# DRV10987.net
KiCad netlist of a schematic drawn in EAGLE
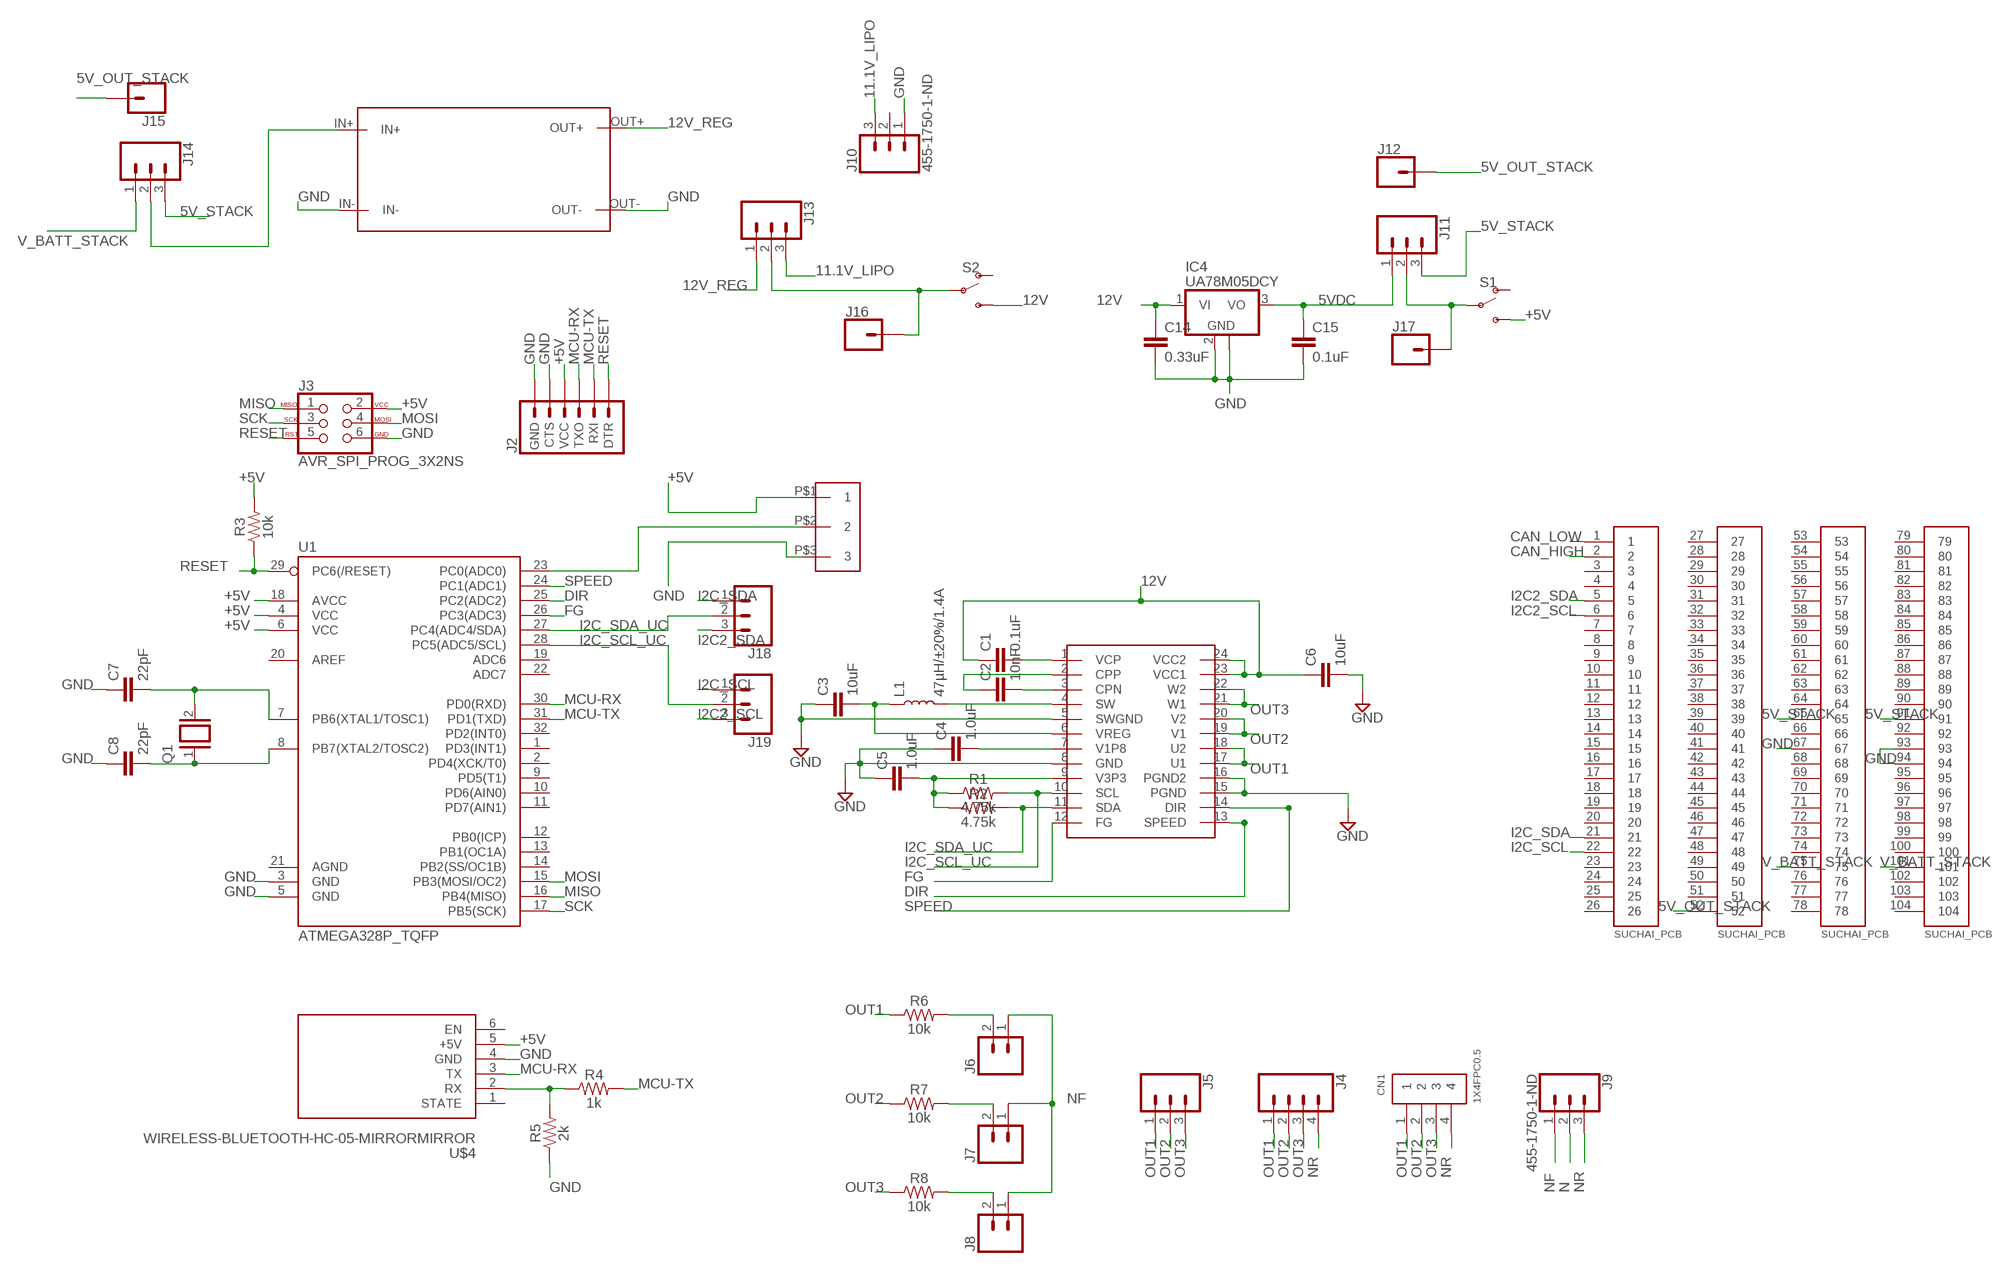
[diagram p0: schematic, sheet 1]

(export (version "E")
  (design (tool "Eeschema 10.0.6"))
  (components
    (comp (ref "C1")
      (value "0.1uF")
      (footprint "eagle-import:0805")
      (libsource (lib "eagle-import") (part "1.0UF-0805-25V-10%"))
    )
    (comp (ref "C2")
      (value "10nF")
      (footprint "eagle-import:0805")
      (libsource (lib "eagle-import") (part "1.0UF-0805-25V-10%"))
    )
    (comp (ref "C3")
      (value "10uF")
      (footprint "eagle-import:0805")
      (libsource (lib "eagle-import") (part "1.0UF-0805-25V-10%"))
    )
    (comp (ref "C4")
      (value "1.0uF")
      (footprint "eagle-import:0805")
      (libsource (lib "eagle-import") (part "1.0UF-0805-25V-10%"))
    )
    (comp (ref "C5")
      (value "1.0uF")
      (footprint "eagle-import:0805")
      (libsource (lib "eagle-import") (part "1.0UF-0805-25V-10%"))
    )
    (comp (ref "C6")
      (value "10uF")
      (footprint "eagle-import:0805")
      (libsource (lib "eagle-import") (part "1.0UF-0805-25V-10%"))
    )
    (comp (ref "C7")
      (value "22pF")
      (footprint "eagle-import:1206")
      (libsource (lib "eagle-import") (part "2.2UF-1206-50V-10%"))
    )
    (comp (ref "C8")
      (value "22pF")
      (footprint "eagle-import:1206")
      (libsource (lib "eagle-import") (part "2.2UF-1206-50V-10%"))
    )
    (comp (ref "C14")
      (value "0.33uF")
      (footprint "eagle-import:1206")
      (libsource (lib "eagle-import") (part "1.0UF-1206-50V-10%"))
    )
    (comp (ref "C15")
      (value "0.1uF")
      (footprint "eagle-import:1206")
      (libsource (lib "eagle-import") (part "1.0UF-1206-50V-10%"))
    )
    (comp (ref "CN1")
      (value "1X4FPC0.5")
      (footprint "eagle-import:FPC_0.5MM-4")
      (libsource (lib "eagle-import") (part "1X4FPC0.5"))
    )
    (comp (ref "IC4")
      (value "UA78M05DCY")
      (footprint "eagle-import:SOT223")
      (libsource (lib "eagle-import") (part "UA78MDCY05"))
    )
    (comp (ref "J1")
      (value "SUCHAI_PCB")
      (footprint "eagle-import:SUCHAI_PCB")
      (libsource (lib "eagle-import") (part "SUCHAI_PCB"))
    )
    (comp (ref "J2")
      (value "6_PIN_SERIAL_TARGET")
      (footprint "eagle-import:1X06")
      (libsource (lib "eagle-import") (part "6_PIN_SERIAL_TARGET"))
    )
    (comp (ref "J3")
      (value "AVR_SPI_PROG_3X2NS")
      (footprint "eagle-import:2X3-NS")
      (libsource (lib "eagle-import") (part "AVR_SPI_PROG_3X2NS"))
    )
    (comp (ref "J4")
      (value "CONN_04")
      (footprint "eagle-import:1X04")
      (libsource (lib "eagle-import") (part "CONN_04"))
    )
    (comp (ref "J5")
      (value "CONN_03-SCREW-5MM")
      (footprint "eagle-import:SCREWTERMINAL-5MM-3")
      (libsource (lib "eagle-import") (part "CONN_03-SCREW-5MM"))
    )
    (comp (ref "J6")
      (value "CONN_02")
      (footprint "eagle-import:1X02")
      (libsource (lib "eagle-import") (part "CONN_02"))
    )
    (comp (ref "J7")
      (value "CONN_02")
      (footprint "eagle-import:1X02")
      (libsource (lib "eagle-import") (part "CONN_02"))
    )
    (comp (ref "J8")
      (value "CONN_02")
      (footprint "eagle-import:1X02")
      (libsource (lib "eagle-import") (part "CONN_02"))
    )
    (comp (ref "J9")
      (value "455-1750-1-ND")
      (footprint "eagle-import:1X03")
      (libsource (lib "eagle-import") (part "CONN_03"))
    )
    (comp (ref "J10")
      (value "455-1750-1-ND")
      (footprint "eagle-import:1X03")
      (libsource (lib "eagle-import") (part "CONN_03"))
    )
    (comp (ref "J11")
      (value "CONN_03LOCK")
      (footprint "eagle-import:1X03_LOCK")
      (libsource (lib "eagle-import") (part "CONN_03LOCK"))
    )
    (comp (ref "J12")
      (value "CONN_01")
      (footprint "eagle-import:1X01")
      (libsource (lib "eagle-import") (part "CONN_01"))
    )
    (comp (ref "J13")
      (value "CONN_03LOCK")
      (footprint "eagle-import:1X03_LOCK")
      (libsource (lib "eagle-import") (part "CONN_03LOCK"))
    )
    (comp (ref "J14")
      (value "CONN_03LOCK")
      (footprint "eagle-import:1X03_LOCK")
      (libsource (lib "eagle-import") (part "CONN_03LOCK"))
    )
    (comp (ref "J15")
      (value "CONN_01")
      (footprint "eagle-import:1X01")
      (libsource (lib "eagle-import") (part "CONN_01"))
    )
    (comp (ref "J16")
      (value "CONN_01")
      (footprint "eagle-import:1X01")
      (libsource (lib "eagle-import") (part "CONN_01"))
    )
    (comp (ref "J17")
      (value "CONN_01")
      (footprint "eagle-import:1X01")
      (libsource (lib "eagle-import") (part "CONN_01"))
    )
    (comp (ref "J18")
      (value "CONN_03LOCK")
      (footprint "eagle-import:1X03_LOCK")
      (libsource (lib "eagle-import") (part "CONN_03LOCK"))
    )
    (comp (ref "J19")
      (value "CONN_03LOCK")
      (footprint "eagle-import:1X03_LOCK")
      (libsource (lib "eagle-import") (part "CONN_03LOCK"))
    )
    (comp (ref "L1")
      (value "47µH/±20%/1.4A")
      (footprint "eagle-import:SRN6045")
      (libsource (lib "eagle-import") (part "INDUCTOR-SRN6045-33UH"))
    )
    (comp (ref "Q1")
      (value "XTAL/S")
      (footprint "eagle-import:QS")
      (libsource (lib "eagle-import") (part "XTAL/S"))
    )
    (comp (ref "R1")
      (value "4.75k")
      (footprint "eagle-import:0805")
      (libsource (lib "eagle-import") (part "RESISTOR0805"))
    )
    (comp (ref "R2")
      (value "4.75k")
      (footprint "eagle-import:0805")
      (libsource (lib "eagle-import") (part "RESISTOR0805"))
    )
    (comp (ref "R3")
      (value "10k")
      (footprint "eagle-import:1206")
      (libsource (lib "eagle-import") (part "RESISTOR1206"))
    )
    (comp (ref "R4")
      (value "1k")
      (footprint "eagle-import:AXIAL-0.3")
      (libsource (lib "eagle-import") (part "1KOHM-HORIZ-1/4W-5%"))
    )
    (comp (ref "R5")
      (value "2k")
      (footprint "eagle-import:AXIAL-0.3")
      (libsource (lib "eagle-import") (part "resistors-longpads_RESISTORAXIAL-0.3"))
    )
    (comp (ref "R6")
      (value "10k")
      (footprint "eagle-import:AXIAL-0.3")
      (libsource (lib "eagle-import") (part "10KOHM-HORIZ-1/4W-1%"))
    )
    (comp (ref "R7")
      (value "10k")
      (footprint "eagle-import:AXIAL-0.3")
      (libsource (lib "eagle-import") (part "10KOHM-HORIZ-1/4W-1%"))
    )
    (comp (ref "R8")
      (value "10k")
      (footprint "eagle-import:AXIAL-0.3")
      (libsource (lib "eagle-import") (part "10KOHM-HORIZ-1/4W-1%"))
    )
    (comp (ref "S1")
      (value "SWITCH-SPDT-PTH-11.6X4.0MM")
      (footprint "eagle-import:SWITCH_SPDT_PTH_11.6X4.0MM")
      (libsource (lib "eagle-import") (part "SWITCH-SPDT-PTH-11.6X4.0MM"))
    )
    (comp (ref "S2")
      (value "SWITCH-SPDT-PTH-11.6X4.0MM")
      (footprint "eagle-import:SWITCH_SPDT_PTH_11.6X4.0MM")
      (libsource (lib "eagle-import") (part "SWITCH-SPDT-PTH-11.6X4.0MM"))
    )
    (comp (ref "U$1")
      (value "DRV10987")
      (footprint "eagle-import:DRV10987")
      (libsource (lib "eagle-import") (part "DRV10987"))
    )
    (comp (ref "U$2")
      (value "XL6009E1_MODULE")
      (footprint "eagle-import:XL6009E1_MODULE")
      (libsource (lib "eagle-import") (part "XL6009E1_MODULE"))
    )
    (comp (ref "U$3")
      (value "CONN_03_SMD_SMALL")
      (footprint "eagle-import:CONN_03_SMD_SMALL")
      (libsource (lib "eagle-import") (part "CONN_03_SMD_SMALL"))
    )
    (comp (ref "U$4")
      (value "WIRELESS-BLUETOOTH-HC-05-MIRRORMIRROR")
      (footprint "eagle-import:WIRELESS-BLUETOOTH-HC-05-MIRROR")
      (libsource (lib "eagle-import") (part "WIRELESS-BLUETOOTH-HC-05-MIRRORMIRROR"))
    )
    (comp (ref "U1")
      (value "ATMEGA328P_TQFP")
      (footprint "eagle-import:TQFP32-08")
      (libsource (lib "eagle-import") (part "ATMEGA328P_TQFP"))
    )
  )
  (nets
    (net (code "1") (name "/+5V") (class "Default")
      (node (ref "J2") (pin "4") (pinfunction "VCC_4") (pintype "passive"))
      (node (ref "J3") (pin "2") (pinfunction "2_2") (pintype "passive"))
      (node (ref "R3") (pin "2") (pinfunction "2_2") (pintype "passive"))
      (node (ref "S1") (pin "3") (pinfunction "S_3") (pintype "passive"))
      (node (ref "U$3") (pin "P$1") (pinfunction "1_P$1") (pintype "bidirectional"))
      (node (ref "U$4") (pin "5") (pinfunction "+5V_5") (pintype "power_in"))
      (node (ref "U1") (pin "18") (pinfunction "AVCC_18") (pintype "bidirectional"))
      (node (ref "U1") (pin "4") (pinfunction "VCC_4") (pintype "bidirectional"))
      (node (ref "U1") (pin "6") (pinfunction "VCC_6") (pintype "bidirectional"))
    )
    (net (code "2") (name "/5VDC") (class "Default")
      (node (ref "C15") (pin "1") (pinfunction "1_1") (pintype "passive"))
      (node (ref "IC4") (pin "3") (pinfunction "VO_3") (pintype "passive"))
      (node (ref "J11") (pin "1") (pinfunction "1_1") (pintype "passive"))
    )
    (net (code "3") (name "/5V_OUT_STACK") (class "Default")
      (node (ref "J1") (pin "52") (pinfunction "52_52") (pintype "bidirectional"))
      (node (ref "J12") (pin "1") (pinfunction "1_1") (pintype "passive"))
      (node (ref "J15") (pin "1") (pinfunction "1_1") (pintype "passive"))
    )
    (net (code "4") (name "/5V_STACK") (class "Default")
      (node (ref "J1") (pin "65") (pinfunction "65_65") (pintype "bidirectional"))
      (node (ref "J1") (pin "91") (pinfunction "91_91") (pintype "bidirectional"))
      (node (ref "J11") (pin "3") (pinfunction "3_3") (pintype "passive"))
      (node (ref "J14") (pin "3") (pinfunction "3_3") (pintype "passive"))
    )
    (net (code "5") (name "/11.1V_LIPO") (class "Default")
      (node (ref "J10") (pin "3") (pinfunction "3_3") (pintype "passive"))
      (node (ref "J13") (pin "3") (pinfunction "3_3") (pintype "passive"))
    )
    (net (code "6") (name "/12V") (class "Default")
      (node (ref "C1") (pin "1") (pinfunction "1_1") (pintype "passive"))
      (node (ref "C14") (pin "1") (pinfunction "1_1") (pintype "passive"))
      (node (ref "C6") (pin "1") (pinfunction "1_1") (pintype "passive"))
      (node (ref "IC4") (pin "1") (pinfunction "VI_1") (pintype "input"))
      (node (ref "S2") (pin "3") (pinfunction "S_3") (pintype "passive"))
      (node (ref "U$1") (pin "23") (pinfunction "VCC1_23") (pintype "bidirectional"))
      (node (ref "U$1") (pin "24") (pinfunction "VCC2_24") (pintype "bidirectional"))
    )
    (net (code "7") (name "/12V_REG") (class "Default")
      (node (ref "J13") (pin "1") (pinfunction "1_1") (pintype "passive"))
      (node (ref "U$2") (pin "OUT+") (pinfunction "OUT+_OUT+") (pintype "bidirectional"))
    )
    (net (code "8") (name "/CAN_HIGH") (class "Default")
      (node (ref "J1") (pin "2") (pinfunction "2_2") (pintype "bidirectional"))
    )
    (net (code "9") (name "/CAN_LOW") (class "Default")
      (node (ref "J1") (pin "1") (pinfunction "1_1") (pintype "bidirectional"))
    )
    (net (code "10") (name "/DIR") (class "Default")
      (node (ref "U$1") (pin "13") (pinfunction "SPEED_13") (pintype "bidirectional"))
      (node (ref "U1") (pin "25") (pinfunction "PC2(ADC2)_25") (pintype "bidirectional"))
    )
    (net (code "11") (name "/FG") (class "Default")
      (node (ref "U$1") (pin "12") (pinfunction "FG_12") (pintype "bidirectional"))
      (node (ref "U1") (pin "26") (pinfunction "PC3(ADC3)_26") (pintype "bidirectional"))
    )
    (net (code "12") (name "/I2C2_SCL") (class "Default")
      (node (ref "J1") (pin "6") (pinfunction "6_6") (pintype "bidirectional"))
      (node (ref "J19") (pin "3") (pinfunction "3_3") (pintype "passive"))
    )
    (net (code "13") (name "/I2C2_SDA") (class "Default")
      (node (ref "J1") (pin "5") (pinfunction "5_5") (pintype "bidirectional"))
      (node (ref "J18") (pin "3") (pinfunction "3_3") (pintype "passive"))
    )
    (net (code "14") (name "/I2C_SCL") (class "Default")
      (node (ref "J1") (pin "22") (pinfunction "22_22") (pintype "bidirectional"))
      (node (ref "J19") (pin "1") (pinfunction "1_1") (pintype "passive"))
    )
    (net (code "15") (name "/I2C_SCL_UC") (class "Default")
      (node (ref "J19") (pin "2") (pinfunction "2_2") (pintype "passive"))
      (node (ref "R1") (pin "2") (pinfunction "2_2") (pintype "passive"))
      (node (ref "U$1") (pin "10") (pinfunction "SCL_10") (pintype "bidirectional"))
      (node (ref "U1") (pin "28") (pinfunction "PC5(ADC5/SCL)_28") (pintype "bidirectional"))
    )
    (net (code "16") (name "/I2C_SDA") (class "Default")
      (node (ref "J1") (pin "21") (pinfunction "21_21") (pintype "bidirectional"))
      (node (ref "J18") (pin "1") (pinfunction "1_1") (pintype "passive"))
    )
    (net (code "17") (name "/I2C_SDA_UC") (class "Default")
      (node (ref "J18") (pin "2") (pinfunction "2_2") (pintype "passive"))
      (node (ref "R2") (pin "2") (pinfunction "2_2") (pintype "passive"))
      (node (ref "U$1") (pin "11") (pinfunction "SDA_11") (pintype "bidirectional"))
      (node (ref "U1") (pin "27") (pinfunction "PC4(ADC4/SDA)_27") (pintype "bidirectional"))
    )
    (net (code "18") (name "/MCU-RX") (class "Default")
      (node (ref "J2") (pin "3") (pinfunction "TXO_3") (pintype "passive"))
      (node (ref "U$4") (pin "3") (pinfunction "TX_3") (pintype "bidirectional"))
      (node (ref "U1") (pin "30") (pinfunction "PD0(RXD)_30") (pintype "bidirectional"))
    )
    (net (code "19") (name "/MCU-TX") (class "Default")
      (node (ref "J2") (pin "2") (pinfunction "RXI_2") (pintype "passive"))
      (node (ref "R4") (pin "P$2") (pinfunction "2_P$2") (pintype "passive"))
      (node (ref "U1") (pin "31") (pinfunction "PD1(TXD)_31") (pintype "bidirectional"))
    )
    (net (code "20") (name "/MISO") (class "Default")
      (node (ref "J3") (pin "1") (pinfunction "1_1") (pintype "passive"))
      (node (ref "U1") (pin "16") (pinfunction "PB4(MISO)_16") (pintype "bidirectional"))
    )
    (net (code "21") (name "/MOSI") (class "Default")
      (node (ref "J3") (pin "4") (pinfunction "4_4") (pintype "passive"))
      (node (ref "U1") (pin "15") (pinfunction "PB3(MOSI/OC2)_15") (pintype "bidirectional"))
    )
    (net (code "22") (name "/N") (class "Default")
      (node (ref "J9") (pin "2") (pinfunction "2_2") (pintype "passive"))
    )
    (net (code "23") (name "/NF") (class "Default")
      (node (ref "J6") (pin "1") (pinfunction "1_1") (pintype "passive"))
      (node (ref "J7") (pin "1") (pinfunction "1_1") (pintype "passive"))
      (node (ref "J8") (pin "1") (pinfunction "1_1") (pintype "passive"))
      (node (ref "J9") (pin "1") (pinfunction "1_1") (pintype "passive"))
    )
    (net (code "24") (name "/NR") (class "Default")
      (node (ref "CN1") (pin "4") (pinfunction "4_4") (pintype "bidirectional"))
      (node (ref "J4") (pin "4") (pinfunction "4_4") (pintype "passive"))
      (node (ref "J9") (pin "3") (pinfunction "3_3") (pintype "passive"))
    )
    (net (code "25") (name "/OUT1") (class "Default")
      (node (ref "CN1") (pin "1") (pinfunction "1_1") (pintype "bidirectional"))
      (node (ref "J4") (pin "1") (pinfunction "1_1") (pintype "passive"))
      (node (ref "J5") (pin "1") (pinfunction "1_1") (pintype "passive"))
      (node (ref "R6") (pin "P$1") (pinfunction "1_P$1") (pintype "passive"))
      (node (ref "U$1") (pin "17") (pinfunction "U1_17") (pintype "bidirectional"))
      (node (ref "U$1") (pin "18") (pinfunction "U2_18") (pintype "bidirectional"))
    )
    (net (code "26") (name "/OUT2") (class "Default")
      (node (ref "CN1") (pin "2") (pinfunction "2_2") (pintype "bidirectional"))
      (node (ref "J4") (pin "2") (pinfunction "2_2") (pintype "passive"))
      (node (ref "J5") (pin "2") (pinfunction "2_2") (pintype "passive"))
      (node (ref "R7") (pin "P$1") (pinfunction "1_P$1") (pintype "passive"))
      (node (ref "U$1") (pin "19") (pinfunction "V1_19") (pintype "bidirectional"))
      (node (ref "U$1") (pin "20") (pinfunction "V2_20") (pintype "bidirectional"))
    )
    (net (code "27") (name "/OUT3") (class "Default")
      (node (ref "CN1") (pin "3") (pinfunction "3_3") (pintype "bidirectional"))
      (node (ref "J4") (pin "3") (pinfunction "3_3") (pintype "passive"))
      (node (ref "J5") (pin "3") (pinfunction "3_3") (pintype "passive"))
      (node (ref "R8") (pin "P$1") (pinfunction "1_P$1") (pintype "passive"))
      (node (ref "U$1") (pin "21") (pinfunction "W1_21") (pintype "bidirectional"))
      (node (ref "U$1") (pin "22") (pinfunction "W2_22") (pintype "bidirectional"))
    )
    (net (code "28") (name "/RESET") (class "Default")
      (node (ref "J2") (pin "1") (pinfunction "DTR_1") (pintype "passive"))
      (node (ref "J3") (pin "5") (pinfunction "5_5") (pintype "passive"))
      (node (ref "R3") (pin "1") (pinfunction "1_1") (pintype "passive"))
      (node (ref "U1") (pin "29") (pinfunction "PC6(/RESET)_29") (pintype "bidirectional"))
    )
    (net (code "29") (name "/SCK") (class "Default")
      (node (ref "J3") (pin "3") (pinfunction "3_3") (pintype "passive"))
      (node (ref "U1") (pin "17") (pinfunction "PB5(SCK)_17") (pintype "bidirectional"))
    )
    (net (code "30") (name "/SPEED") (class "Default")
      (node (ref "U$1") (pin "14") (pinfunction "DIR_14") (pintype "bidirectional"))
      (node (ref "U1") (pin "24") (pinfunction "PC1(ADC1)_24") (pintype "bidirectional"))
    )
    (net (code "31") (name "/V_BATT_STACK") (class "Default")
      (node (ref "J1") (pin "101") (pinfunction "101_101") (pintype "bidirectional"))
      (node (ref "J1") (pin "75") (pinfunction "75_75") (pintype "bidirectional"))
      (node (ref "J14") (pin "1") (pinfunction "1_1") (pintype "passive"))
    )
    (net (code "32") (name "GND") (class "Default")
      (node (ref "C14") (pin "2") (pinfunction "2_2") (pintype "passive"))
      (node (ref "C15") (pin "2") (pinfunction "2_2") (pintype "passive"))
      (node (ref "C3") (pin "1") (pinfunction "1_1") (pintype "passive"))
      (node (ref "C4") (pin "1") (pinfunction "1_1") (pintype "passive"))
      (node (ref "C5") (pin "1") (pinfunction "1_1") (pintype "passive"))
      (node (ref "C6") (pin "2") (pinfunction "2_2") (pintype "passive"))
      (node (ref "C7") (pin "1") (pinfunction "1_1") (pintype "passive"))
      (node (ref "C8") (pin "1") (pinfunction "1_1") (pintype "passive"))
      (node (ref "IC4") (pin "2") (pinfunction "GND_2") (pintype "passive"))
      (node (ref "IC4") (pin "4") (pinfunction "GND_4") (pintype "passive"))
      (node (ref "J1") (pin "67") (pinfunction "67_67") (pintype "bidirectional"))
      (node (ref "J1") (pin "93") (pinfunction "93_93") (pintype "bidirectional"))
      (node (ref "J1") (pin "94") (pinfunction "94_94") (pintype "bidirectional"))
      (node (ref "J10") (pin "1") (pinfunction "1_1") (pintype "passive"))
      (node (ref "J2") (pin "5") (pinfunction "CTS_5") (pintype "passive"))
      (node (ref "J2") (pin "6") (pinfunction "GND_6") (pintype "passive"))
      (node (ref "J3") (pin "6") (pinfunction "6_6") (pintype "passive"))
      (node (ref "R5") (pin "P$1") (pinfunction "1_P$1") (pintype "passive"))
      (node (ref "U$1") (pin "15") (pinfunction "PGND_15") (pintype "bidirectional"))
      (node (ref "U$1") (pin "16") (pinfunction "PGND2_16") (pintype "bidirectional"))
      (node (ref "U$1") (pin "5") (pinfunction "SWGND_5") (pintype "bidirectional"))
      (node (ref "U$1") (pin "8") (pinfunction "GND_8") (pintype "bidirectional"))
      (node (ref "U$2") (pin "IN-") (pinfunction "IN-_IN-") (pintype "bidirectional"))
      (node (ref "U$2") (pin "OUT-") (pinfunction "OUT-_OUT-") (pintype "bidirectional"))
      (node (ref "U$3") (pin "P$3") (pinfunction "3_P$3") (pintype "bidirectional"))
      (node (ref "U$4") (pin "4") (pinfunction "GND_4") (pintype "power_in"))
      (node (ref "U1") (pin "3") (pinfunction "GND_3") (pintype "bidirectional"))
      (node (ref "U1") (pin "5") (pinfunction "GND_5") (pintype "bidirectional"))
    )
    (net (code "33") (name "Net-(J14-Pad2)") (class "Default")
      (node (ref "J14") (pin "2") (pinfunction "2_2") (pintype "passive"))
      (node (ref "U$2") (pin "IN+") (pinfunction "IN+_IN+") (pintype "bidirectional"))
    )
    (net (code "34") (name "Net-(R4-1)") (class "Default")
      (node (ref "R4") (pin "P$1") (pinfunction "1_P$1") (pintype "passive"))
      (node (ref "R5") (pin "P$2") (pinfunction "2_P$2") (pintype "passive"))
      (node (ref "U$4") (pin "2") (pinfunction "RX_2") (pintype "bidirectional"))
    )
    (net (code "35") (name "Net-(R6-2)") (class "Default")
      (node (ref "J6") (pin "2") (pinfunction "2_2") (pintype "passive"))
      (node (ref "R6") (pin "P$2") (pinfunction "2_P$2") (pintype "passive"))
    )
    (net (code "36") (name "Net-(R7-2)") (class "Default")
      (node (ref "J7") (pin "2") (pinfunction "2_2") (pintype "passive"))
      (node (ref "R7") (pin "P$2") (pinfunction "2_P$2") (pintype "passive"))
    )
    (net (code "37") (name "Net-(R8-2)") (class "Default")
      (node (ref "J8") (pin "2") (pinfunction "2_2") (pintype "passive"))
      (node (ref "R8") (pin "P$2") (pinfunction "2_P$2") (pintype "passive"))
    )
    (net (code "38") (name "Net-(S1-P)") (class "Default")
      (node (ref "J11") (pin "2") (pinfunction "2_2") (pintype "passive"))
      (node (ref "J17") (pin "1") (pinfunction "1_1") (pintype "passive"))
      (node (ref "S1") (pin "2") (pinfunction "P_2") (pintype "passive"))
    )
    (net (code "39") (name "Net-(S2-P)") (class "Default")
      (node (ref "J13") (pin "2") (pinfunction "2_2") (pintype "passive"))
      (node (ref "J16") (pin "1") (pinfunction "1_1") (pintype "passive"))
      (node (ref "S2") (pin "2") (pinfunction "P_2") (pintype "passive"))
    )
    (net (code "40") (name "Net-(U$1-CPN)") (class "Default")
      (node (ref "C2") (pin "2") (pinfunction "2_2") (pintype "passive"))
      (node (ref "U$1") (pin "3") (pinfunction "CPN_3") (pintype "bidirectional"))
    )
    (net (code "41") (name "Net-(U$1-CPP)") (class "Default")
      (node (ref "C2") (pin "1") (pinfunction "1_1") (pintype "passive"))
      (node (ref "U$1") (pin "2") (pinfunction "CPP_2") (pintype "bidirectional"))
    )
    (net (code "42") (name "Net-(U$1-SW)") (class "Default")
      (node (ref "L1") (pin "2") (pinfunction "2_2") (pintype "passive"))
      (node (ref "U$1") (pin "4") (pinfunction "SW_4") (pintype "bidirectional"))
    )
    (net (code "43") (name "Net-(U$1-V1P8)") (class "Default")
      (node (ref "C4") (pin "2") (pinfunction "2_2") (pintype "passive"))
      (node (ref "U$1") (pin "7") (pinfunction "V1P8_7") (pintype "bidirectional"))
    )
    (net (code "44") (name "Net-(U$1-V3P3)") (class "Default")
      (node (ref "C5") (pin "2") (pinfunction "2_2") (pintype "passive"))
      (node (ref "R1") (pin "1") (pinfunction "1_1") (pintype "passive"))
      (node (ref "R2") (pin "1") (pinfunction "1_1") (pintype "passive"))
      (node (ref "U$1") (pin "9") (pinfunction "V3P3_9") (pintype "bidirectional"))
    )
    (net (code "45") (name "Net-(U$1-VCP)") (class "Default")
      (node (ref "C1") (pin "2") (pinfunction "2_2") (pintype "passive"))
      (node (ref "U$1") (pin "1") (pinfunction "VCP_1") (pintype "bidirectional"))
    )
    (net (code "46") (name "Net-(U$1-VREG)") (class "Default")
      (node (ref "C3") (pin "2") (pinfunction "2_2") (pintype "passive"))
      (node (ref "L1") (pin "1") (pinfunction "1_1") (pintype "passive"))
      (node (ref "U$1") (pin "6") (pinfunction "VREG_6") (pintype "bidirectional"))
    )
    (net (code "47") (name "Net-(U$3-2)") (class "Default")
      (node (ref "U$3") (pin "P$2") (pinfunction "2_P$2") (pintype "bidirectional"))
      (node (ref "U1") (pin "23") (pinfunction "PC0(ADC0)_23") (pintype "bidirectional"))
    )
    (net (code "48") (name "Net-(U1-PB6(XTAL1{slash}TOSC1))") (class "Default")
      (node (ref "C7") (pin "2") (pinfunction "2_2") (pintype "passive"))
      (node (ref "Q1") (pin "2") (pinfunction "2_2") (pintype "passive"))
      (node (ref "U1") (pin "7") (pinfunction "PB6(XTAL1/TOSC1)_7") (pintype "bidirectional"))
    )
    (net (code "49") (name "Net-(U1-PB7(XTAL2{slash}TOSC2))") (class "Default")
      (node (ref "C8") (pin "2") (pinfunction "2_2") (pintype "passive"))
      (node (ref "Q1") (pin "1") (pinfunction "1_1") (pintype "passive"))
      (node (ref "U1") (pin "8") (pinfunction "PB7(XTAL2/TOSC2)_8") (pintype "bidirectional"))
    )
    (net (code "50") (name "unconnected-(J1-Pad3)") (class "Default")
      (node (ref "J1") (pin "3") (pinfunction "3_3") (pintype "bidirectional"))
    )
    (net (code "51") (name "unconnected-(J1-Pad4)") (class "Default")
      (node (ref "J1") (pin "4") (pinfunction "4_4") (pintype "bidirectional"))
    )
    (net (code "52") (name "unconnected-(J1-Pad7)") (class "Default")
      (node (ref "J1") (pin "7") (pinfunction "7_7") (pintype "bidirectional"))
    )
    (net (code "53") (name "unconnected-(J1-Pad8)") (class "Default")
      (node (ref "J1") (pin "8") (pinfunction "8_8") (pintype "bidirectional"))
    )
    (net (code "54") (name "unconnected-(J1-Pad9)") (class "Default")
      (node (ref "J1") (pin "9") (pinfunction "9_9") (pintype "bidirectional"))
    )
    (net (code "55") (name "unconnected-(J1-Pad10)") (class "Default")
      (node (ref "J1") (pin "10") (pinfunction "10_10") (pintype "bidirectional"))
    )
    (net (code "56") (name "unconnected-(J1-Pad11)") (class "Default")
      (node (ref "J1") (pin "11") (pinfunction "11_11") (pintype "bidirectional"))
    )
    (net (code "57") (name "unconnected-(J1-Pad12)") (class "Default")
      (node (ref "J1") (pin "12") (pinfunction "12_12") (pintype "bidirectional"))
    )
    (net (code "58") (name "unconnected-(J1-Pad13)") (class "Default")
      (node (ref "J1") (pin "13") (pinfunction "13_13") (pintype "bidirectional"))
    )
    (net (code "59") (name "unconnected-(J1-Pad14)") (class "Default")
      (node (ref "J1") (pin "14") (pinfunction "14_14") (pintype "bidirectional"))
    )
    (net (code "60") (name "unconnected-(J1-Pad15)") (class "Default")
      (node (ref "J1") (pin "15") (pinfunction "15_15") (pintype "bidirectional"))
    )
    (net (code "61") (name "unconnected-(J1-Pad16)") (class "Default")
      (node (ref "J1") (pin "16") (pinfunction "16_16") (pintype "bidirectional"))
    )
    (net (code "62") (name "unconnected-(J1-Pad17)") (class "Default")
      (node (ref "J1") (pin "17") (pinfunction "17_17") (pintype "bidirectional"))
    )
    (net (code "63") (name "unconnected-(J1-Pad18)") (class "Default")
      (node (ref "J1") (pin "18") (pinfunction "18_18") (pintype "bidirectional"))
    )
    (net (code "64") (name "unconnected-(J1-Pad19)") (class "Default")
      (node (ref "J1") (pin "19") (pinfunction "19_19") (pintype "bidirectional"))
    )
    (net (code "65") (name "unconnected-(J1-Pad20)") (class "Default")
      (node (ref "J1") (pin "20") (pinfunction "20_20") (pintype "bidirectional"))
    )
    (net (code "66") (name "unconnected-(J1-Pad23)") (class "Default")
      (node (ref "J1") (pin "23") (pinfunction "23_23") (pintype "bidirectional"))
    )
    (net (code "67") (name "unconnected-(J1-Pad24)") (class "Default")
      (node (ref "J1") (pin "24") (pinfunction "24_24") (pintype "bidirectional"))
    )
    (net (code "68") (name "unconnected-(J1-Pad25)") (class "Default")
      (node (ref "J1") (pin "25") (pinfunction "25_25") (pintype "bidirectional"))
    )
    (net (code "69") (name "unconnected-(J1-Pad26)") (class "Default")
      (node (ref "J1") (pin "26") (pinfunction "26_26") (pintype "bidirectional"))
    )
    (net (code "70") (name "unconnected-(J1-Pad27)") (class "Default")
      (node (ref "J1") (pin "27") (pinfunction "27_27") (pintype "bidirectional"))
    )
    (net (code "71") (name "unconnected-(J1-Pad28)") (class "Default")
      (node (ref "J1") (pin "28") (pinfunction "28_28") (pintype "bidirectional"))
    )
    (net (code "72") (name "unconnected-(J1-Pad29)") (class "Default")
      (node (ref "J1") (pin "29") (pinfunction "29_29") (pintype "bidirectional"))
    )
    (net (code "73") (name "unconnected-(J1-Pad30)") (class "Default")
      (node (ref "J1") (pin "30") (pinfunction "30_30") (pintype "bidirectional"))
    )
    (net (code "74") (name "unconnected-(J1-Pad31)") (class "Default")
      (node (ref "J1") (pin "31") (pinfunction "31_31") (pintype "bidirectional"))
    )
    (net (code "75") (name "unconnected-(J1-Pad32)") (class "Default")
      (node (ref "J1") (pin "32") (pinfunction "32_32") (pintype "bidirectional"))
    )
    (net (code "76") (name "unconnected-(J1-Pad33)") (class "Default")
      (node (ref "J1") (pin "33") (pinfunction "33_33") (pintype "bidirectional"))
    )
    (net (code "77") (name "unconnected-(J1-Pad34)") (class "Default")
      (node (ref "J1") (pin "34") (pinfunction "34_34") (pintype "bidirectional"))
    )
    (net (code "78") (name "unconnected-(J1-Pad35)") (class "Default")
      (node (ref "J1") (pin "35") (pinfunction "35_35") (pintype "bidirectional"))
    )
    (net (code "79") (name "unconnected-(J1-Pad36)") (class "Default")
      (node (ref "J1") (pin "36") (pinfunction "36_36") (pintype "bidirectional"))
    )
    (net (code "80") (name "unconnected-(J1-Pad37)") (class "Default")
      (node (ref "J1") (pin "37") (pinfunction "37_37") (pintype "bidirectional"))
    )
    (net (code "81") (name "unconnected-(J1-Pad38)") (class "Default")
      (node (ref "J1") (pin "38") (pinfunction "38_38") (pintype "bidirectional"))
    )
    (net (code "82") (name "unconnected-(J1-Pad39)") (class "Default")
      (node (ref "J1") (pin "39") (pinfunction "39_39") (pintype "bidirectional"))
    )
    (net (code "83") (name "unconnected-(J1-Pad40)") (class "Default")
      (node (ref "J1") (pin "40") (pinfunction "40_40") (pintype "bidirectional"))
    )
    (net (code "84") (name "unconnected-(J1-Pad41)") (class "Default")
      (node (ref "J1") (pin "41") (pinfunction "41_41") (pintype "bidirectional"))
    )
    (net (code "85") (name "unconnected-(J1-Pad42)") (class "Default")
      (node (ref "J1") (pin "42") (pinfunction "42_42") (pintype "bidirectional"))
    )
    (net (code "86") (name "unconnected-(J1-Pad43)") (class "Default")
      (node (ref "J1") (pin "43") (pinfunction "43_43") (pintype "bidirectional"))
    )
    (net (code "87") (name "unconnected-(J1-Pad44)") (class "Default")
      (node (ref "J1") (pin "44") (pinfunction "44_44") (pintype "bidirectional"))
    )
    (net (code "88") (name "unconnected-(J1-Pad45)") (class "Default")
      (node (ref "J1") (pin "45") (pinfunction "45_45") (pintype "bidirectional"))
    )
    (net (code "89") (name "unconnected-(J1-Pad46)") (class "Default")
      (node (ref "J1") (pin "46") (pinfunction "46_46") (pintype "bidirectional"))
    )
    (net (code "90") (name "unconnected-(J1-Pad47)") (class "Default")
      (node (ref "J1") (pin "47") (pinfunction "47_47") (pintype "bidirectional"))
    )
    (net (code "91") (name "unconnected-(J1-Pad48)") (class "Default")
      (node (ref "J1") (pin "48") (pinfunction "48_48") (pintype "bidirectional"))
    )
    (net (code "92") (name "unconnected-(J1-Pad49)") (class "Default")
      (node (ref "J1") (pin "49") (pinfunction "49_49") (pintype "bidirectional"))
    )
    (net (code "93") (name "unconnected-(J1-Pad50)") (class "Default")
      (node (ref "J1") (pin "50") (pinfunction "50_50") (pintype "bidirectional"))
    )
    (net (code "94") (name "unconnected-(J1-Pad51)") (class "Default")
      (node (ref "J1") (pin "51") (pinfunction "51_51") (pintype "bidirectional"))
    )
    (net (code "95") (name "unconnected-(J1-Pad53)") (class "Default")
      (node (ref "J1") (pin "53") (pinfunction "53_53") (pintype "bidirectional"))
    )
    (net (code "96") (name "unconnected-(J1-Pad54)") (class "Default")
      (node (ref "J1") (pin "54") (pinfunction "54_54") (pintype "bidirectional"))
    )
    (net (code "97") (name "unconnected-(J1-Pad55)") (class "Default")
      (node (ref "J1") (pin "55") (pinfunction "55_55") (pintype "bidirectional"))
    )
    (net (code "98") (name "unconnected-(J1-Pad56)") (class "Default")
      (node (ref "J1") (pin "56") (pinfunction "56_56") (pintype "bidirectional"))
    )
    (net (code "99") (name "unconnected-(J1-Pad57)") (class "Default")
      (node (ref "J1") (pin "57") (pinfunction "57_57") (pintype "bidirectional"))
    )
    (net (code "100") (name "unconnected-(J1-Pad58)") (class "Default")
      (node (ref "J1") (pin "58") (pinfunction "58_58") (pintype "bidirectional"))
    )
    (net (code "101") (name "unconnected-(J1-Pad59)") (class "Default")
      (node (ref "J1") (pin "59") (pinfunction "59_59") (pintype "bidirectional"))
    )
    (net (code "102") (name "unconnected-(J1-Pad60)") (class "Default")
      (node (ref "J1") (pin "60") (pinfunction "60_60") (pintype "bidirectional"))
    )
    (net (code "103") (name "unconnected-(J1-Pad61)") (class "Default")
      (node (ref "J1") (pin "61") (pinfunction "61_61") (pintype "bidirectional"))
    )
    (net (code "104") (name "unconnected-(J1-Pad62)") (class "Default")
      (node (ref "J1") (pin "62") (pinfunction "62_62") (pintype "bidirectional"))
    )
    (net (code "105") (name "unconnected-(J1-Pad63)") (class "Default")
      (node (ref "J1") (pin "63") (pinfunction "63_63") (pintype "bidirectional"))
    )
    (net (code "106") (name "unconnected-(J1-Pad64)") (class "Default")
      (node (ref "J1") (pin "64") (pinfunction "64_64") (pintype "bidirectional"))
    )
    (net (code "107") (name "unconnected-(J1-Pad66)") (class "Default")
      (node (ref "J1") (pin "66") (pinfunction "66_66") (pintype "bidirectional"))
    )
    (net (code "108") (name "unconnected-(J1-Pad68)") (class "Default")
      (node (ref "J1") (pin "68") (pinfunction "68_68") (pintype "bidirectional"))
    )
    (net (code "109") (name "unconnected-(J1-Pad69)") (class "Default")
      (node (ref "J1") (pin "69") (pinfunction "69_69") (pintype "bidirectional"))
    )
    (net (code "110") (name "unconnected-(J1-Pad70)") (class "Default")
      (node (ref "J1") (pin "70") (pinfunction "70_70") (pintype "bidirectional"))
    )
    (net (code "111") (name "unconnected-(J1-Pad71)") (class "Default")
      (node (ref "J1") (pin "71") (pinfunction "71_71") (pintype "bidirectional"))
    )
    (net (code "112") (name "unconnected-(J1-Pad72)") (class "Default")
      (node (ref "J1") (pin "72") (pinfunction "72_72") (pintype "bidirectional"))
    )
    (net (code "113") (name "unconnected-(J1-Pad73)") (class "Default")
      (node (ref "J1") (pin "73") (pinfunction "73_73") (pintype "bidirectional"))
    )
    (net (code "114") (name "unconnected-(J1-Pad74)") (class "Default")
      (node (ref "J1") (pin "74") (pinfunction "74_74") (pintype "bidirectional"))
    )
    (net (code "115") (name "unconnected-(J1-Pad76)") (class "Default")
      (node (ref "J1") (pin "76") (pinfunction "76_76") (pintype "bidirectional"))
    )
    (net (code "116") (name "unconnected-(J1-Pad77)") (class "Default")
      (node (ref "J1") (pin "77") (pinfunction "77_77") (pintype "bidirectional"))
    )
    (net (code "117") (name "unconnected-(J1-Pad78)") (class "Default")
      (node (ref "J1") (pin "78") (pinfunction "78_78") (pintype "bidirectional"))
    )
    (net (code "118") (name "unconnected-(J1-Pad79)") (class "Default")
      (node (ref "J1") (pin "79") (pinfunction "79_79") (pintype "bidirectional"))
    )
    (net (code "119") (name "unconnected-(J1-Pad80)") (class "Default")
      (node (ref "J1") (pin "80") (pinfunction "80_80") (pintype "bidirectional"))
    )
    (net (code "120") (name "unconnected-(J1-Pad81)") (class "Default")
      (node (ref "J1") (pin "81") (pinfunction "81_81") (pintype "bidirectional"))
    )
    (net (code "121") (name "unconnected-(J1-Pad82)") (class "Default")
      (node (ref "J1") (pin "82") (pinfunction "82_82") (pintype "bidirectional"))
    )
    (net (code "122") (name "unconnected-(J1-Pad83)") (class "Default")
      (node (ref "J1") (pin "83") (pinfunction "83_83") (pintype "bidirectional"))
    )
    (net (code "123") (name "unconnected-(J1-Pad84)") (class "Default")
      (node (ref "J1") (pin "84") (pinfunction "84_84") (pintype "bidirectional"))
    )
    (net (code "124") (name "unconnected-(J1-Pad85)") (class "Default")
      (node (ref "J1") (pin "85") (pinfunction "85_85") (pintype "bidirectional"))
    )
    (net (code "125") (name "unconnected-(J1-Pad86)") (class "Default")
      (node (ref "J1") (pin "86") (pinfunction "86_86") (pintype "bidirectional"))
    )
    (net (code "126") (name "unconnected-(J1-Pad87)") (class "Default")
      (node (ref "J1") (pin "87") (pinfunction "87_87") (pintype "bidirectional"))
    )
    (net (code "127") (name "unconnected-(J1-Pad88)") (class "Default")
      (node (ref "J1") (pin "88") (pinfunction "88_88") (pintype "bidirectional"))
    )
    (net (code "128") (name "unconnected-(J1-Pad89)") (class "Default")
      (node (ref "J1") (pin "89") (pinfunction "89_89") (pintype "bidirectional"))
    )
    (net (code "129") (name "unconnected-(J1-Pad90)") (class "Default")
      (node (ref "J1") (pin "90") (pinfunction "90_90") (pintype "bidirectional"))
    )
    (net (code "130") (name "unconnected-(J1-Pad92)") (class "Default")
      (node (ref "J1") (pin "92") (pinfunction "92_92") (pintype "bidirectional"))
    )
    (net (code "131") (name "unconnected-(J1-Pad95)") (class "Default")
      (node (ref "J1") (pin "95") (pinfunction "95_95") (pintype "bidirectional"))
    )
    (net (code "132") (name "unconnected-(J1-Pad96)") (class "Default")
      (node (ref "J1") (pin "96") (pinfunction "96_96") (pintype "bidirectional"))
    )
    (net (code "133") (name "unconnected-(J1-Pad97)") (class "Default")
      (node (ref "J1") (pin "97") (pinfunction "97_97") (pintype "bidirectional"))
    )
    (net (code "134") (name "unconnected-(J1-Pad98)") (class "Default")
      (node (ref "J1") (pin "98") (pinfunction "98_98") (pintype "bidirectional"))
    )
    (net (code "135") (name "unconnected-(J1-Pad99)") (class "Default")
      (node (ref "J1") (pin "99") (pinfunction "99_99") (pintype "bidirectional"))
    )
    (net (code "136") (name "unconnected-(J1-Pad100)") (class "Default")
      (node (ref "J1") (pin "100") (pinfunction "100_100") (pintype "bidirectional"))
    )
    (net (code "137") (name "unconnected-(J1-Pad102)") (class "Default")
      (node (ref "J1") (pin "102") (pinfunction "102_102") (pintype "bidirectional"))
    )
    (net (code "138") (name "unconnected-(J1-Pad103)") (class "Default")
      (node (ref "J1") (pin "103") (pinfunction "103_103") (pintype "bidirectional"))
    )
    (net (code "139") (name "unconnected-(J1-Pad104)") (class "Default")
      (node (ref "J1") (pin "104") (pinfunction "104_104") (pintype "bidirectional"))
    )
    (net (code "140") (name "unconnected-(J10-Pad2)") (class "Default")
      (node (ref "J10") (pin "2") (pinfunction "2_2") (pintype "passive"))
    )
    (net (code "141") (name "unconnected-(S1-O-Pad1)") (class "Default")
      (node (ref "S1") (pin "1") (pinfunction "O_1") (pintype "passive"))
    )
    (net (code "142") (name "unconnected-(S2-O-Pad1)") (class "Default")
      (node (ref "S2") (pin "1") (pinfunction "O_1") (pintype "passive"))
    )
    (net (code "143") (name "unconnected-(U$4-EN-Pad6)") (class "Default")
      (node (ref "U$4") (pin "6") (pinfunction "EN_6") (pintype "bidirectional"))
    )
    (net (code "144") (name "unconnected-(U$4-STATE-Pad1)") (class "Default")
      (node (ref "U$4") (pin "1") (pinfunction "STATE_1") (pintype "bidirectional"))
    )
    (net (code "145") (name "unconnected-(U1-ADC6-Pad19)") (class "Default")
      (node (ref "U1") (pin "19") (pinfunction "ADC6_19") (pintype "bidirectional"))
    )
    (net (code "146") (name "unconnected-(U1-ADC7-Pad22)") (class "Default")
      (node (ref "U1") (pin "22") (pinfunction "ADC7_22") (pintype "bidirectional"))
    )
    (net (code "147") (name "unconnected-(U1-AGND-Pad21)") (class "Default")
      (node (ref "U1") (pin "21") (pinfunction "AGND_21") (pintype "bidirectional"))
    )
    (net (code "148") (name "unconnected-(U1-AREF-Pad20)") (class "Default")
      (node (ref "U1") (pin "20") (pinfunction "AREF_20") (pintype "bidirectional"))
    )
    (net (code "149") (name "unconnected-(U1-PB0(ICP)-Pad12)") (class "Default")
      (node (ref "U1") (pin "12") (pinfunction "PB0(ICP)_12") (pintype "bidirectional"))
    )
    (net (code "150") (name "unconnected-(U1-PB1(OC1A)-Pad13)") (class "Default")
      (node (ref "U1") (pin "13") (pinfunction "PB1(OC1A)_13") (pintype "bidirectional"))
    )
    (net (code "151") (name "unconnected-(U1-PB2(SS{slash}OC1B)-Pad14)") (class "Default")
      (node (ref "U1") (pin "14") (pinfunction "PB2(SS/OC1B)_14") (pintype "bidirectional"))
    )
    (net (code "152") (name "unconnected-(U1-PD2(INT0)-Pad32)") (class "Default")
      (node (ref "U1") (pin "32") (pinfunction "PD2(INT0)_32") (pintype "bidirectional"))
    )
    (net (code "153") (name "unconnected-(U1-PD3(INT1)-Pad1)") (class "Default")
      (node (ref "U1") (pin "1") (pinfunction "PD3(INT1)_1") (pintype "bidirectional"))
    )
    (net (code "154") (name "unconnected-(U1-PD4(XCK{slash}T0)-Pad2)") (class "Default")
      (node (ref "U1") (pin "2") (pinfunction "PD4(XCK/T0)_2") (pintype "bidirectional"))
    )
    (net (code "155") (name "unconnected-(U1-PD5(T1)-Pad9)") (class "Default")
      (node (ref "U1") (pin "9") (pinfunction "PD5(T1)_9") (pintype "bidirectional"))
    )
    (net (code "156") (name "unconnected-(U1-PD6(AIN0)-Pad10)") (class "Default")
      (node (ref "U1") (pin "10") (pinfunction "PD6(AIN0)_10") (pintype "bidirectional"))
    )
    (net (code "157") (name "unconnected-(U1-PD7(AIN1)-Pad11)") (class "Default")
      (node (ref "U1") (pin "11") (pinfunction "PD7(AIN1)_11") (pintype "bidirectional"))
    )
  )
)
